# Power.net
KiCad netlist of a schematic drawn in Altium Designer
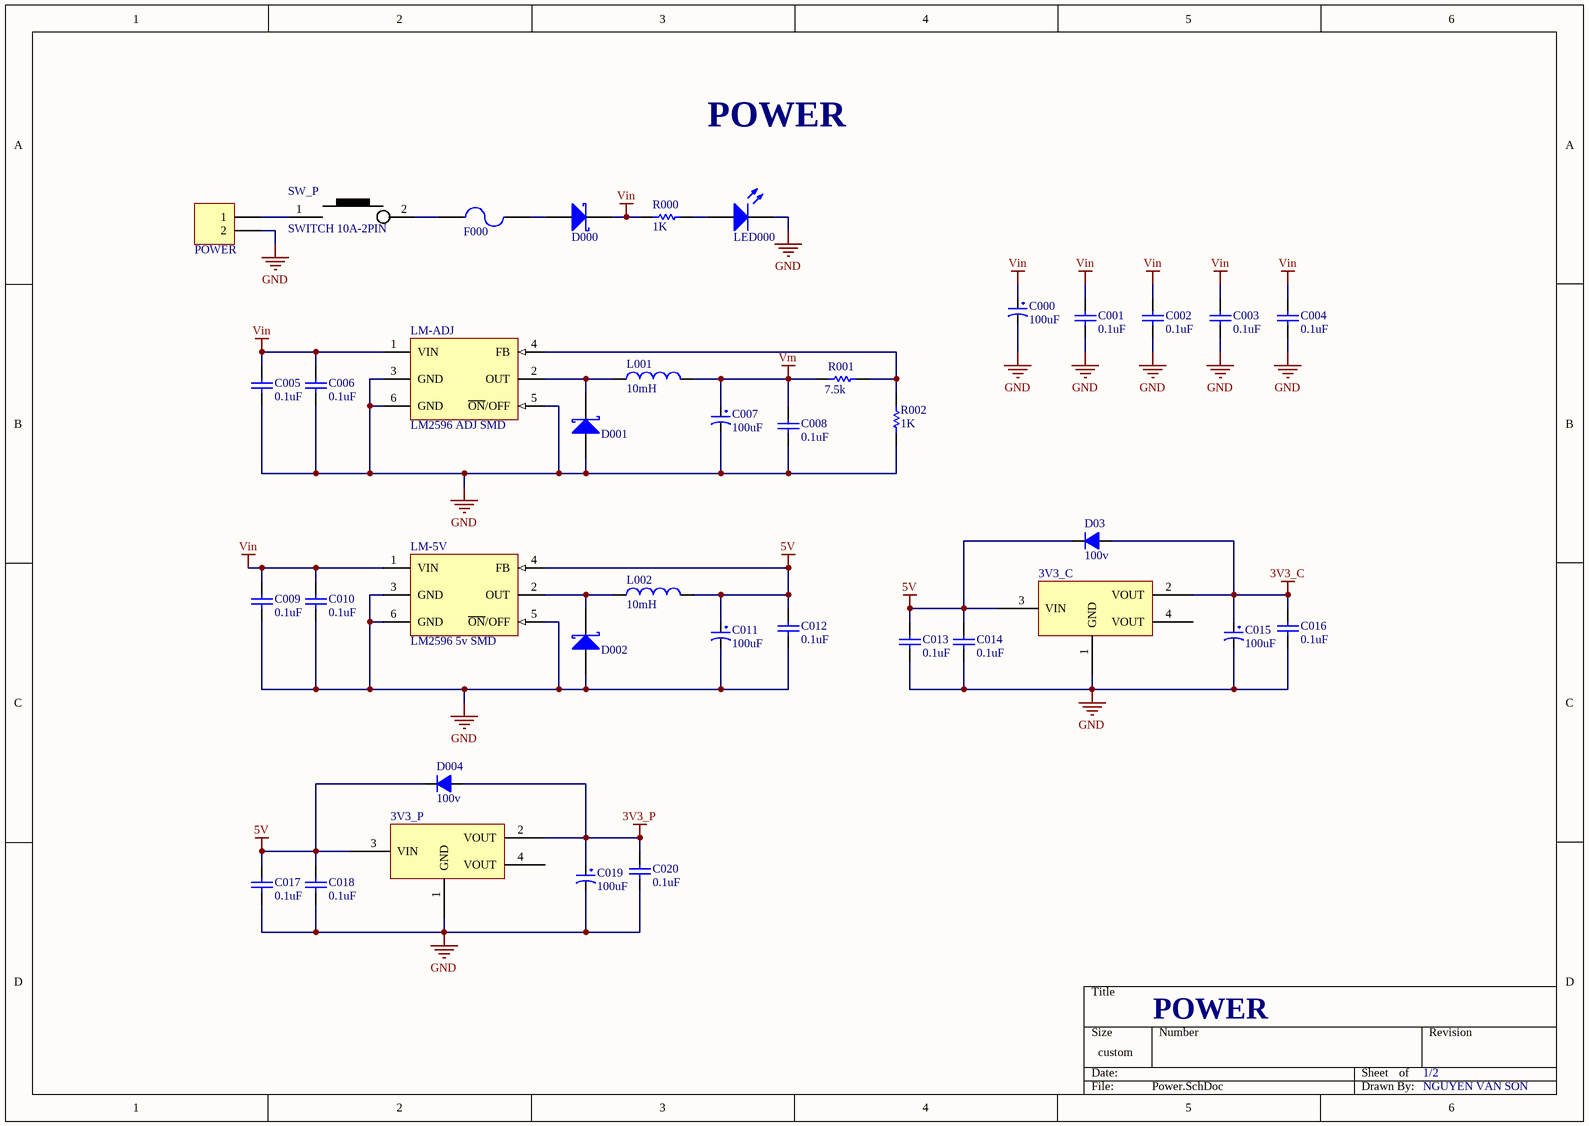
[diagram p0: Power.SchDoc]

(export (version "E")
  (design (tool "Eeschema 10.0.6"))
  (components
    (comp (ref "3V3_C")
      (value "AMS1117-3.3V")
      (footprint "SOT223")
      (description "Dán")
      (libsource (lib "Altium_Lib_by_KhueNguyenCreator") (part "AMS1117 SMD"))
    )
    (comp (ref "3V3_P")
      (value "AMS1117-3.3V")
      (footprint "SOT223")
      (description "Dán")
      (libsource (lib "Altium_Lib_by_KhueNguyenCreator") (part "AMS1117 SMD"))
    )
    (comp (ref "C000")
      (value "100uF")
      (footprint "tu tantalum smd7343")
      (description "Dán")
      (libsource (lib "Altium_Lib_by_KhueNguyenCreator") (part "Tu tantalum 100uF 50V SMD7343"))
    )
    (comp (ref "C001")
      (value "0.1uF")
      (footprint "CAP-SM-0603")
      (description "Capacitor")
      (fields (field (name "Comment") "Cap Non-Pol SMD"))
      (libsource (lib "PIF_Library") (part "Cap Non-Pol SMD"))
    )
    (comp (ref "C002")
      (value "0.1uF")
      (footprint "CAP-SM-0603")
      (description "Capacitor")
      (fields (field (name "Comment") "Cap Non-Pol SMD"))
      (libsource (lib "PIF_Library") (part "Cap Non-Pol SMD"))
    )
    (comp (ref "C003")
      (value "0.1uF")
      (footprint "CAP-SM-0603")
      (description "Capacitor")
      (fields (field (name "Comment") "Cap Non-Pol SMD"))
      (libsource (lib "PIF_Library") (part "Cap Non-Pol SMD"))
    )
    (comp (ref "C004")
      (value "0.1uF")
      (footprint "CAP-SM-0603")
      (description "Capacitor")
      (fields (field (name "Comment") "Cap Non-Pol SMD"))
      (libsource (lib "PIF_Library") (part "Cap Non-Pol SMD"))
    )
    (comp (ref "C005")
      (value "0.1uF")
      (footprint "CAP-SM-0603")
      (description "Capacitor")
      (fields (field (name "Comment") "Cap Non-Pol SMD"))
      (libsource (lib "PIF_Library") (part "Cap Non-Pol SMD"))
    )
    (comp (ref "C006")
      (value "0.1uF")
      (footprint "CAP-SM-0603")
      (description "Capacitor")
      (fields (field (name "Comment") "Cap Non-Pol SMD"))
      (libsource (lib "PIF_Library") (part "Cap Non-Pol SMD"))
    )
    (comp (ref "C007")
      (value "100uF")
      (footprint "tu tantalum smd3528")
      (description "Dán")
      (libsource (lib "Altium_Lib_by_KhueNguyenCreator") (part "Tu tantalum 100uF 50V SMD7343"))
    )
    (comp (ref "C008")
      (value "0.1uF")
      (footprint "CAP-SM-0603")
      (description "Capacitor")
      (fields (field (name "Comment") "Cap Non-Pol SMD"))
      (libsource (lib "PIF_Library") (part "Cap Non-Pol SMD"))
    )
    (comp (ref "C009")
      (value "0.1uF")
      (footprint "CAP-SM-0603")
      (description "Capacitor")
      (fields (field (name "Comment") "Cap Non-Pol SMD"))
      (libsource (lib "PIF_Library") (part "Cap Non-Pol SMD"))
    )
    (comp (ref "C010")
      (value "0.1uF")
      (footprint "CAP-SM-0603")
      (description "Capacitor")
      (fields (field (name "Comment") "Cap Non-Pol SMD"))
      (libsource (lib "PIF_Library") (part "Cap Non-Pol SMD"))
    )
    (comp (ref "C011")
      (value "100uF")
      (footprint "tu tantalum smd3528")
      (description "Dán")
      (libsource (lib "Altium_Lib_by_KhueNguyenCreator") (part "Tu tantalum 100uF 10V SMD6032"))
    )
    (comp (ref "C012")
      (value "0.1uF")
      (footprint "CAP-SM-0603")
      (description "Capacitor")
      (fields (field (name "Comment") "Cap Non-Pol SMD"))
      (libsource (lib "PIF_Library") (part "Cap Non-Pol SMD"))
    )
    (comp (ref "C013")
      (value "0.1uF")
      (footprint "CAP-SM-0603")
      (description "Capacitor")
      (fields (field (name "Comment") "Cap Non-Pol SMD"))
      (libsource (lib "PIF_Library") (part "Cap Non-Pol SMD"))
    )
    (comp (ref "C014")
      (value "0.1uF")
      (footprint "CAP-SM-0603")
      (description "Capacitor")
      (fields (field (name "Comment") "Cap Non-Pol SMD"))
      (libsource (lib "PIF_Library") (part "Cap Non-Pol SMD"))
    )
    (comp (ref "C015")
      (value "100uF")
      (footprint "tu tantalum smd3528")
      (description "Dán")
      (libsource (lib "Altium_Lib_by_KhueNguyenCreator") (part "Tu tantalum 100uF 6.3V SMD3528"))
    )
    (comp (ref "C016")
      (value "0.1uF")
      (footprint "CAP-SM-0603")
      (description "Capacitor")
      (fields (field (name "Comment") "Cap Non-Pol SMD"))
      (libsource (lib "PIF_Library") (part "Cap Non-Pol SMD"))
    )
    (comp (ref "C017")
      (value "0.1uF")
      (footprint "CAP-SM-0603")
      (description "Capacitor")
      (fields (field (name "Comment") "Cap Non-Pol SMD"))
      (libsource (lib "PIF_Library") (part "Cap Non-Pol SMD"))
    )
    (comp (ref "C018")
      (value "0.1uF")
      (footprint "CAP-SM-0603")
      (description "Capacitor")
      (fields (field (name "Comment") "Cap Non-Pol SMD"))
      (libsource (lib "PIF_Library") (part "Cap Non-Pol SMD"))
    )
    (comp (ref "C019")
      (value "100uF")
      (footprint "tu tantalum smd3528")
      (description "Dán")
      (libsource (lib "Altium_Lib_by_KhueNguyenCreator") (part "Tu tantalum 100uF 6.3V SMD3528"))
    )
    (comp (ref "C020")
      (value "0.1uF")
      (footprint "CAP-SM-0603")
      (description "Capacitor")
      (fields (field (name "Comment") "Cap Non-Pol SMD"))
      (libsource (lib "PIF_Library") (part "Cap Non-Pol SMD"))
    )
    (comp (ref "D000")
      (value "D Schottky")
      (footprint "SS34")
      (description "Schottky Diode")
      (fields (field (name "PUBLISHER") "Altium Limited"))
      (libsource (lib "PIF_Library") (part "D Schottky"))
    )
    (comp (ref "D001")
      (value "D Schottky")
      (footprint "SS34")
      (description "Schottky Diode")
      (fields (field (name "PUBLISHER") "Altium Limited"))
      (libsource (lib "PIF_Library") (part "D Schottky"))
    )
    (comp (ref "D002")
      (value "D Schottky")
      (footprint "SS34")
      (description "Schottky Diode")
      (fields (field (name "PUBLISHER") "Altium Limited"))
      (libsource (lib "PIF_Library") (part "D Schottky"))
    )
    (comp (ref "D03")
      (value "100v")
      (footprint "DIODE SMA")
      (description "Cắm")
      (libsource (lib "Altium_Lib_by_KhueNguyenCreator") (part "Diode 1N4007"))
    )
    (comp (ref "D004")
      (value "100v")
      (footprint "DIODE SMA")
      (description "Cắm")
      (libsource (lib "Altium_Lib_by_KhueNguyenCreator") (part "Diode 1N4007"))
    )
    (comp (ref "F000") (value "Fuse") (footprint "FUSE SMD") (libsource (lib "PIF_Library") (part "Fuse")))
    (comp (ref "L001")
      (value "10mH")
      (footprint "INDUCTOR 12.5x12.5")
      (description "Inductor")
      (libsource (lib "PIF_Library") (part "Inductor"))
    )
    (comp (ref "L002")
      (value "10mH")
      (footprint "INDUCTOR 12.5x12.5")
      (description "Inductor")
      (libsource (lib "PIF_Library") (part "Inductor"))
    )
    (comp (ref "LED000")
      (value "LED SMD")
      (footprint "LED_0805_Blue")
      (description "LED")
      (libsource (lib "PIF_Library") (part "LED SMD"))
    )
    (comp (ref "LM-5V")
      (value "LM2596 5v SMD")
      (footprint "TO263-5")
      (description "Dán")
      (libsource (lib "Altium_Lib_by_KhueNguyenCreator") (part "LM2576 3.3V SMD"))
    )
    (comp (ref "LM-ADJ")
      (value "LM2596 ADJ SMD")
      (footprint "TO263-5")
      (description "Dán")
      (libsource (lib "Altium_Lib_by_KhueNguyenCreator") (part "LM2576 3.3V SMD"))
    )
    (comp (ref "POWER")
      (value "Domino 2")
      (footprint "DOMINO SMALL 2")
      (description "Domino, 2-Pin")
      (fields (field (name "PUBLISHER") "Altium Limited"))
      (libsource (lib "PIF_Library") (part "Domino 2"))
    )
    (comp (ref "R000")
      (value "1K")
      (footprint "RES-SM-0603")
      (description "Resistor")
      (fields (field (name "Comment") "RESISTOR SMD"))
      (libsource (lib "PIF_Library") (part "RESISTOR SMD"))
    )
    (comp (ref "R001")
      (value "7.5k")
      (footprint "RES-SM-0603")
      (description "Resistor")
      (fields (field (name "Comment") "RESISTOR SMD"))
      (libsource (lib "PIF_Library") (part "RESISTOR SMD"))
    )
    (comp (ref "R002")
      (value "1K")
      (footprint "RES-SM-0603")
      (description "Resistor")
      (fields (field (name "Comment") "RESISTOR SMD"))
      (libsource (lib "PIF_Library") (part "RESISTOR SMD"))
    )
    (comp (ref "SW_P")
      (value "SWITCH 10A-2PIN")
      (footprint "SW_2ARS_TH")
      (description "Rocker Switch SPST 16A (AC), 10A (DC) 250V Panel Mount, Snap-In")
      (fields
        (field (name "MANUFACTURER") "Würth Elektronik")
        (field (name "MANUFACTURER PART NUMBER") "471005264153")
      )
      (libsource (lib "Altium_Lib_by_KhueNguyenCreator") (part "SW1_RS-471005264153-TH"))
    )
  )
  (nets
    (net (code "1") (name "3V3_C") (class "Default")
      (node (ref "3V3_C") (pin "2") (pinfunction "VOUT_2") (pintype "passive"))
      (node (ref "C015") (pin "1") (pinfunction "1_1") (pintype "passive"))
      (node (ref "C016") (pin "2") (pinfunction "2_2") (pintype "passive"))
      (node (ref "D03") (pin "1") (pinfunction "A_1") (pintype "passive"))
    )
    (net (code "2") (name "3V3_P") (class "Default")
      (node (ref "3V3_P") (pin "2") (pinfunction "VOUT_2") (pintype "passive"))
      (node (ref "C019") (pin "1") (pinfunction "1_1") (pintype "passive"))
      (node (ref "C020") (pin "2") (pinfunction "2_2") (pintype "passive"))
      (node (ref "D004") (pin "1") (pinfunction "A_1") (pintype "passive"))
    )
    (net (code "3") (name "5V") (class "Default")
      (node (ref "3V3_C") (pin "3") (pinfunction "VIN_3") (pintype "passive"))
      (node (ref "3V3_P") (pin "3") (pinfunction "VIN_3") (pintype "passive"))
      (node (ref "C011") (pin "1") (pinfunction "1_1") (pintype "passive"))
      (node (ref "C012") (pin "2") (pinfunction "2_2") (pintype "passive"))
      (node (ref "C013") (pin "2") (pinfunction "2_2") (pintype "passive"))
      (node (ref "C014") (pin "2") (pinfunction "2_2") (pintype "passive"))
      (node (ref "C017") (pin "2") (pinfunction "2_2") (pintype "passive"))
      (node (ref "C018") (pin "2") (pinfunction "2_2") (pintype "passive"))
      (node (ref "D004") (pin "2") (pinfunction "K_2") (pintype "passive"))
      (node (ref "D03") (pin "2") (pinfunction "K_2") (pintype "passive"))
      (node (ref "L002") (pin "2") (pinfunction "2_2") (pintype "passive"))
      (node (ref "LM-5V") (pin "4") (pinfunction "FB_4") (pintype "input"))
    )
    (net (code "4") (name "GND") (class "Default")
      (node (ref "3V3_C") (pin "1") (pinfunction "GND_1") (pintype "passive"))
      (node (ref "3V3_P") (pin "1") (pinfunction "GND_1") (pintype "passive"))
      (node (ref "C000") (pin "2") (pinfunction "2_2") (pintype "passive"))
      (node (ref "C001") (pin "1") (pinfunction "1_1") (pintype "passive"))
      (node (ref "C002") (pin "1") (pinfunction "1_1") (pintype "passive"))
      (node (ref "C003") (pin "1") (pinfunction "1_1") (pintype "passive"))
      (node (ref "C004") (pin "1") (pinfunction "1_1") (pintype "passive"))
      (node (ref "C005") (pin "1") (pinfunction "1_1") (pintype "passive"))
      (node (ref "C006") (pin "1") (pinfunction "1_1") (pintype "passive"))
      (node (ref "C007") (pin "2") (pinfunction "2_2") (pintype "passive"))
      (node (ref "C008") (pin "1") (pinfunction "1_1") (pintype "passive"))
      (node (ref "C009") (pin "1") (pinfunction "1_1") (pintype "passive"))
      (node (ref "C010") (pin "1") (pinfunction "1_1") (pintype "passive"))
      (node (ref "C011") (pin "2") (pinfunction "2_2") (pintype "passive"))
      (node (ref "C012") (pin "1") (pinfunction "1_1") (pintype "passive"))
      (node (ref "C013") (pin "1") (pinfunction "1_1") (pintype "passive"))
      (node (ref "C014") (pin "1") (pinfunction "1_1") (pintype "passive"))
      (node (ref "C015") (pin "2") (pinfunction "2_2") (pintype "passive"))
      (node (ref "C016") (pin "1") (pinfunction "1_1") (pintype "passive"))
      (node (ref "C017") (pin "1") (pinfunction "1_1") (pintype "passive"))
      (node (ref "C018") (pin "1") (pinfunction "1_1") (pintype "passive"))
      (node (ref "C019") (pin "2") (pinfunction "2_2") (pintype "passive"))
      (node (ref "C020") (pin "1") (pinfunction "1_1") (pintype "passive"))
      (node (ref "D001") (pin "1") (pinfunction "A_1") (pintype "passive"))
      (node (ref "D002") (pin "1") (pinfunction "A_1") (pintype "passive"))
      (node (ref "LED000") (pin "2") (pinfunction "K_2") (pintype "passive"))
      (node (ref "LM-5V") (pin "3") (pinfunction "GND_3") (pintype "power_in"))
      (node (ref "LM-5V") (pin "5") (pinfunction "~{ON}/OFF_5") (pintype "input"))
      (node (ref "LM-5V") (pin "6") (pinfunction "GND_6") (pintype "passive"))
      (node (ref "LM-ADJ") (pin "3") (pinfunction "GND_3") (pintype "power_in"))
      (node (ref "LM-ADJ") (pin "5") (pinfunction "~{ON}/OFF_5") (pintype "input"))
      (node (ref "LM-ADJ") (pin "6") (pinfunction "GND_6") (pintype "passive"))
      (node (ref "POWER") (pin "2") (pinfunction "2_2") (pintype "passive"))
      (node (ref "R002") (pin "2") (pinfunction "2_2") (pintype "passive"))
    )
    (net (code "5") (name "Net-(D000-A)") (class "Default")
      (node (ref "D000") (pin "1") (pinfunction "A_1") (pintype "passive"))
      (node (ref "F000") (pin "2") (pinfunction "2_2") (pintype "passive"))
    )
    (net (code "6") (name "Net-(D001-K)") (class "Default")
      (node (ref "D001") (pin "2") (pinfunction "K_2") (pintype "passive"))
      (node (ref "L001") (pin "1") (pinfunction "1_1") (pintype "passive"))
      (node (ref "LM-ADJ") (pin "2") (pinfunction "OUT_2") (pintype "power_in"))
    )
    (net (code "7") (name "Net-(D002-K)") (class "Default")
      (node (ref "D002") (pin "2") (pinfunction "K_2") (pintype "passive"))
      (node (ref "L002") (pin "1") (pinfunction "1_1") (pintype "passive"))
      (node (ref "LM-5V") (pin "2") (pinfunction "OUT_2") (pintype "power_in"))
    )
    (net (code "8") (name "Net-(F000-Pad1)") (class "Default")
      (node (ref "F000") (pin "1") (pinfunction "1_1") (pintype "passive"))
      (node (ref "SW_P") (pin "2") (pinfunction "2_2") (pintype "passive"))
    )
    (net (code "9") (name "Net-(LED000-A)") (class "Default")
      (node (ref "LED000") (pin "1") (pinfunction "A_1") (pintype "passive"))
      (node (ref "R000") (pin "2") (pinfunction "2_2") (pintype "passive"))
    )
    (net (code "10") (name "Net-(LM-ADJ-FB)") (class "Default")
      (node (ref "LM-ADJ") (pin "4") (pinfunction "FB_4") (pintype "input"))
      (node (ref "R001") (pin "1") (pinfunction "1_1") (pintype "passive"))
      (node (ref "R002") (pin "1") (pinfunction "1_1") (pintype "passive"))
    )
    (net (code "11") (name "Net-(POWER-Pad1)") (class "Default")
      (node (ref "POWER") (pin "1") (pinfunction "1_1") (pintype "passive"))
      (node (ref "SW_P") (pin "1") (pinfunction "1_1") (pintype "passive"))
    )
    (net (code "12") (name "Vin") (class "Default")
      (node (ref "C000") (pin "1") (pinfunction "1_1") (pintype "passive"))
      (node (ref "C001") (pin "2") (pinfunction "2_2") (pintype "passive"))
      (node (ref "C002") (pin "2") (pinfunction "2_2") (pintype "passive"))
      (node (ref "C003") (pin "2") (pinfunction "2_2") (pintype "passive"))
      (node (ref "C004") (pin "2") (pinfunction "2_2") (pintype "passive"))
      (node (ref "C005") (pin "2") (pinfunction "2_2") (pintype "passive"))
      (node (ref "C006") (pin "2") (pinfunction "2_2") (pintype "passive"))
      (node (ref "C009") (pin "2") (pinfunction "2_2") (pintype "passive"))
      (node (ref "C010") (pin "2") (pinfunction "2_2") (pintype "passive"))
      (node (ref "D000") (pin "2") (pinfunction "K_2") (pintype "passive"))
      (node (ref "LM-5V") (pin "1") (pinfunction "VIN_1") (pintype "power_in"))
      (node (ref "LM-ADJ") (pin "1") (pinfunction "VIN_1") (pintype "power_in"))
      (node (ref "R000") (pin "1") (pinfunction "1_1") (pintype "passive"))
    )
    (net (code "13") (name "Vm") (class "Default")
      (node (ref "C007") (pin "1") (pinfunction "1_1") (pintype "passive"))
      (node (ref "C008") (pin "2") (pinfunction "2_2") (pintype "passive"))
      (node (ref "L001") (pin "2") (pinfunction "2_2") (pintype "passive"))
      (node (ref "R001") (pin "2") (pinfunction "2_2") (pintype "passive"))
    )
    (net (code "14") (name "unconnected-(3V3_C-VOUT-Pad4)") (class "Default")
      (node (ref "3V3_C") (pin "4") (pinfunction "VOUT_4") (pintype "passive"))
    )
    (net (code "15") (name "unconnected-(3V3_P-VOUT-Pad4)") (class "Default")
      (node (ref "3V3_P") (pin "4") (pinfunction "VOUT_4") (pintype "passive"))
    )
  )
)
